# Node.net
KiCad netlist of a schematic drawn in EAGLE
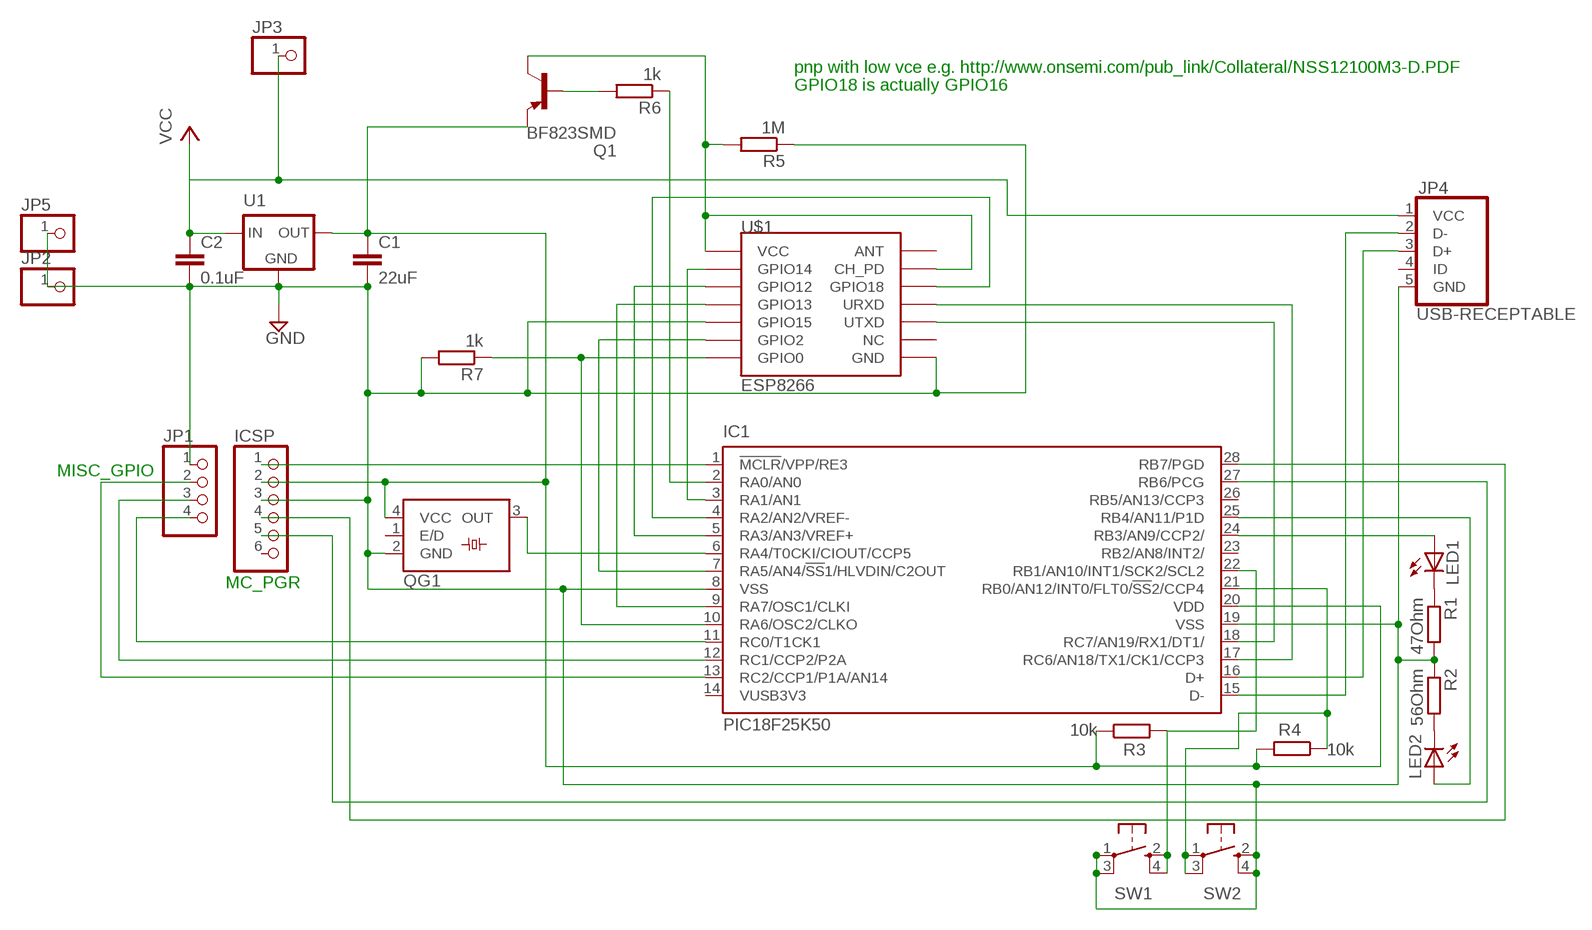
[diagram p0: schematic, sheet 1]

(export (version "E")
  (design (tool "Eeschema 10.0.6"))
  (components
    (comp (ref "C1")
      (value "22uF")
      (footprint "eagle-import:C0805")
      (libsource (lib "eagle-import") (part "C-EUC0805"))
    )
    (comp (ref "C2")
      (value "0.1uF")
      (footprint "eagle-import:C0805")
      (libsource (lib "eagle-import") (part "C-EUC0805"))
    )
    (comp (ref "IC1")
      (value "PIC18F25K50")
      (footprint "eagle-import:SO28W")
      (libsource (lib "eagle-import") (part "PIC18F25K50/SO-I"))
    )
    (comp (ref "ICSP")
      (value "PINHD-1X6")
      (footprint "eagle-import:1X06")
      (libsource (lib "eagle-import") (part "PINHD-1X6"))
    )
    (comp (ref "JP1")
      (value "PINHD-1X4")
      (footprint "eagle-import:1X04")
      (libsource (lib "eagle-import") (part "PINHD-1X4"))
    )
    (comp (ref "JP2")
      (value "PINHD-1X1")
      (footprint "eagle-import:1X01")
      (libsource (lib "eagle-import") (part "PINHD-1X1"))
    )
    (comp (ref "JP3")
      (value "PINHD-1X1")
      (footprint "eagle-import:1X01")
      (libsource (lib "eagle-import") (part "PINHD-1X1"))
    )
    (comp (ref "JP4")
      (value "USB-RECEPTABLE")
      (footprint "eagle-import:FCI-10103594-0001LF")
      (libsource (lib "eagle-import") (part "USB-RECEPTABLE"))
    )
    (comp (ref "JP5")
      (value "PINHD-1X1")
      (footprint "eagle-import:1X01")
      (libsource (lib "eagle-import") (part "PINHD-1X1"))
    )
    (comp (ref "LED1")
      (value "LEDCHIPLED_0805")
      (footprint "eagle-import:CHIPLED_0805")
      (libsource (lib "eagle-import") (part "LEDCHIPLED_0805"))
    )
    (comp (ref "LED2")
      (value "LEDCHIPLED_0805")
      (footprint "eagle-import:CHIPLED_0805")
      (libsource (lib "eagle-import") (part "LEDCHIPLED_0805"))
    )
    (comp (ref "Q1")
      (value "BF823SMD")
      (footprint "eagle-import:SOT23-BEC")
      (libsource (lib "eagle-import") (part "BF823SMD"))
    )
    (comp (ref "QG1")
      (value "SM77H")
      (footprint "eagle-import:SM77H")
      (libsource (lib "eagle-import") (part "SM77H"))
    )
    (comp (ref "R1")
      (value "47Ohm")
      (footprint "eagle-import:M0805")
      (libsource (lib "eagle-import") (part "R-EU_M0805"))
    )
    (comp (ref "R2")
      (value "56Ohm")
      (footprint "eagle-import:M0805")
      (libsource (lib "eagle-import") (part "R-EU_M0805"))
    )
    (comp (ref "R3")
      (value "10k")
      (footprint "eagle-import:M0805")
      (libsource (lib "eagle-import") (part "R-EU_M0805"))
    )
    (comp (ref "R4")
      (value "10k")
      (footprint "eagle-import:M0805")
      (libsource (lib "eagle-import") (part "R-EU_M0805"))
    )
    (comp (ref "R5")
      (value "1M")
      (footprint "eagle-import:M0805")
      (libsource (lib "eagle-import") (part "R-EU_M0805"))
    )
    (comp (ref "R6")
      (value "1k")
      (footprint "eagle-import:M0805")
      (libsource (lib "eagle-import") (part "R-EU_M0805"))
    )
    (comp (ref "R7")
      (value "1k")
      (footprint "eagle-import:M0805")
      (libsource (lib "eagle-import") (part "R-EU_M0805"))
    )
    (comp (ref "SW1")
      (value "SPST_TACT-KMR2")
      (footprint "eagle-import:KMR2")
      (libsource (lib "eagle-import") (part "SPST_TACT-KMR2"))
    )
    (comp (ref "SW2")
      (value "SPST_TACT-KMR2")
      (footprint "eagle-import:KMR2")
      (libsource (lib "eagle-import") (part "SPST_TACT-KMR2"))
    )
    (comp (ref "U$1")
      (value "ESP8266")
      (footprint "eagle-import:ESP-03")
      (libsource (lib "eagle-import") (part "ESP8266"))
    )
    (comp (ref "U1")
      (value "MIC5209-X.XYS")
      (footprint "eagle-import:SOT223")
      (libsource (lib "eagle-import") (part "MIC5209-X.XYS"))
    )
  )
  (nets
    (net (code "1") (name "GND") (class "Default")
      (node (ref "C1") (pin "2") (pinfunction "2_2") (pintype "passive"))
      (node (ref "C2") (pin "2") (pinfunction "2_2") (pintype "passive"))
      (node (ref "IC1") (pin "19") (pinfunction "VSS_19") (pintype "power_in"))
      (node (ref "IC1") (pin "8") (pinfunction "VSS_8") (pintype "power_in"))
      (node (ref "ICSP") (pin "3") (pinfunction "3_3") (pintype "passive"))
      (node (ref "JP1") (pin "1") (pinfunction "1_1") (pintype "passive"))
      (node (ref "JP2") (pin "1") (pinfunction "1_1") (pintype "passive"))
      (node (ref "JP4") (pin "5") (pinfunction "GND_5") (pintype "bidirectional"))
      (node (ref "JP5") (pin "1") (pinfunction "1_1") (pintype "passive"))
      (node (ref "QG1") (pin "2") (pinfunction "GND_2") (pintype "power_in"))
      (node (ref "R1") (pin "2") (pinfunction "2_2") (pintype "passive"))
      (node (ref "R2") (pin "1") (pinfunction "1_1") (pintype "passive"))
      (node (ref "R5") (pin "1") (pinfunction "1_1") (pintype "passive"))
      (node (ref "R7") (pin "2") (pinfunction "2_2") (pintype "passive"))
      (node (ref "SW1") (pin "1") (pinfunction "P_1") (pintype "passive"))
      (node (ref "SW1") (pin "3") (pinfunction "P1_3") (pintype "passive"))
      (node (ref "SW2") (pin "2") (pinfunction "S_2") (pintype "passive"))
      (node (ref "SW2") (pin "4") (pinfunction "S1_4") (pintype "passive"))
      (node (ref "U$1") (pin "GND") (pinfunction "GND_GND") (pintype "bidirectional"))
      (node (ref "U$1") (pin "GPIO15") (pinfunction "GPIO15_GPIO15") (pintype "bidirectional"))
      (node (ref "U1") (pin "2") (pinfunction "GND_2") (pintype "passive"))
      (node (ref "U1") (pin "4") (pinfunction "GND_4") (pintype "passive"))
    )
    (net (code "2") (name "Net-(IC1-D+)") (class "Default")
      (node (ref "IC1") (pin "16") (pinfunction "D+_16") (pintype "bidirectional"))
      (node (ref "JP4") (pin "3") (pinfunction "D+_3") (pintype "bidirectional"))
    )
    (net (code "3") (name "Net-(IC1-D-)") (class "Default")
      (node (ref "IC1") (pin "15") (pinfunction "D-_15") (pintype "bidirectional"))
      (node (ref "JP4") (pin "2") (pinfunction "D-_2") (pintype "bidirectional"))
    )
    (net (code "4") (name "Net-(IC1-RA0{slash}AN0)") (class "Default")
      (node (ref "IC1") (pin "2") (pinfunction "RA0/AN0_2") (pintype "bidirectional"))
      (node (ref "R6") (pin "1") (pinfunction "1_1") (pintype "passive"))
    )
    (net (code "5") (name "Net-(IC1-RA1{slash}AN1)") (class "Default")
      (node (ref "IC1") (pin "3") (pinfunction "RA1/AN1_3") (pintype "bidirectional"))
      (node (ref "U$1") (pin "GPIO14") (pinfunction "GPIO14_GPIO14") (pintype "bidirectional"))
    )
    (net (code "6") (name "Net-(IC1-RA2{slash}AN2{slash}VREF-)") (class "Default")
      (node (ref "IC1") (pin "4") (pinfunction "RA2/AN2/VREF-_4") (pintype "bidirectional"))
      (node (ref "U$1") (pin "GPIO18") (pinfunction "GPIO18_GPIO18") (pintype "bidirectional"))
    )
    (net (code "7") (name "Net-(IC1-RA3{slash}AN3{slash}VREF+)") (class "Default")
      (node (ref "IC1") (pin "5") (pinfunction "RA3/AN3/VREF+_5") (pintype "bidirectional"))
      (node (ref "U$1") (pin "GPIO12") (pinfunction "GPIO12_GPIO12") (pintype "bidirectional"))
    )
    (net (code "8") (name "Net-(IC1-RA4{slash}T0CKI{slash}CIOUT{slash}CCP5)") (class "Default")
      (node (ref "IC1") (pin "6") (pinfunction "RA4/T0CKI/CIOUT/CCP5_6") (pintype "bidirectional"))
      (node (ref "QG1") (pin "3") (pinfunction "OUT_3") (pintype "output"))
    )
    (net (code "9") (name "Net-(IC1-RA5{slash}AN4{slash}~{SS}1{slash}HLVDIN{slash}C2OUT)") (class "Default")
      (node (ref "IC1") (pin "7") (pinfunction "RA5/AN4/~{SS}1/HLVDIN/C2OUT_7") (pintype "bidirectional"))
      (node (ref "U$1") (pin "GPIO2") (pinfunction "GPIO2_GPIO2") (pintype "bidirectional"))
    )
    (net (code "10") (name "Net-(IC1-RA6{slash}OSC2{slash}CLKO)") (class "Default")
      (node (ref "IC1") (pin "10") (pinfunction "RA6/OSC2/CLKO_10") (pintype "output"))
      (node (ref "R7") (pin "1") (pinfunction "1_1") (pintype "passive"))
      (node (ref "U$1") (pin "GPIO0") (pinfunction "GPIO0_GPIO0") (pintype "bidirectional"))
    )
    (net (code "11") (name "Net-(IC1-RA7{slash}OSC1{slash}CLKI)") (class "Default")
      (node (ref "IC1") (pin "9") (pinfunction "RA7/OSC1/CLKI_9") (pintype "input"))
      (node (ref "U$1") (pin "GPIO13") (pinfunction "GPIO13_GPIO13") (pintype "bidirectional"))
    )
    (net (code "12") (name "Net-(IC1-RB0{slash}AN12{slash}INT0{slash}FLT0{slash}~{SS}2{slash}CCP4)") (class "Default")
      (node (ref "IC1") (pin "21") (pinfunction "RB0/AN12/INT0/FLT0/~{SS}2/CCP4_21") (pintype "bidirectional"))
      (node (ref "R4") (pin "1") (pinfunction "1_1") (pintype "passive"))
      (node (ref "SW2") (pin "1") (pinfunction "P_1") (pintype "passive"))
      (node (ref "SW2") (pin "3") (pinfunction "P1_3") (pintype "passive"))
    )
    (net (code "13") (name "Net-(IC1-RB1{slash}AN10{slash}INT1{slash}SCK2{slash}SCL2)") (class "Default")
      (node (ref "IC1") (pin "22") (pinfunction "RB1/AN10/INT1/SCK2/SCL2_22") (pintype "bidirectional"))
      (node (ref "R3") (pin "2") (pinfunction "2_2") (pintype "passive"))
      (node (ref "SW1") (pin "2") (pinfunction "S_2") (pintype "passive"))
      (node (ref "SW1") (pin "4") (pinfunction "S1_4") (pintype "passive"))
    )
    (net (code "14") (name "Net-(IC1-RB3{slash}AN9{slash}CCP2{slash})") (class "Default")
      (node (ref "IC1") (pin "24") (pinfunction "RB3/AN9/CCP2/_24") (pintype "bidirectional"))
      (node (ref "LED1") (pin "A") (pinfunction "A_A") (pintype "passive"))
    )
    (net (code "15") (name "Net-(IC1-RB4{slash}AN11{slash}P1D)") (class "Default")
      (node (ref "IC1") (pin "25") (pinfunction "RB4/AN11/P1D_25") (pintype "bidirectional"))
      (node (ref "LED2") (pin "A") (pinfunction "A_A") (pintype "passive"))
    )
    (net (code "16") (name "Net-(IC1-RB6{slash}PCG)") (class "Default")
      (node (ref "IC1") (pin "27") (pinfunction "RB6/PCG_27") (pintype "bidirectional"))
      (node (ref "ICSP") (pin "5") (pinfunction "5_5") (pintype "passive"))
    )
    (net (code "17") (name "Net-(IC1-RB7{slash}PGD)") (class "Default")
      (node (ref "IC1") (pin "28") (pinfunction "RB7/PGD_28") (pintype "bidirectional"))
      (node (ref "ICSP") (pin "4") (pinfunction "4_4") (pintype "passive"))
    )
    (net (code "18") (name "Net-(IC1-RC0{slash}T1CK1)") (class "Default")
      (node (ref "IC1") (pin "11") (pinfunction "RC0/T1CK1_11") (pintype "bidirectional"))
      (node (ref "JP1") (pin "4") (pinfunction "4_4") (pintype "passive"))
    )
    (net (code "19") (name "Net-(IC1-RC1{slash}CCP2{slash}P2A)") (class "Default")
      (node (ref "IC1") (pin "12") (pinfunction "RC1/CCP2/P2A_12") (pintype "bidirectional"))
      (node (ref "JP1") (pin "3") (pinfunction "3_3") (pintype "passive"))
    )
    (net (code "20") (name "Net-(IC1-RC2{slash}CCP1{slash}P1A{slash}AN14)") (class "Default")
      (node (ref "IC1") (pin "13") (pinfunction "RC2/CCP1/P1A/AN14_13") (pintype "bidirectional"))
      (node (ref "JP1") (pin "2") (pinfunction "2_2") (pintype "passive"))
    )
    (net (code "21") (name "Net-(IC1-RC6{slash}AN18{slash}TX1{slash}CK1{slash}CCP3)") (class "Default")
      (node (ref "IC1") (pin "17") (pinfunction "RC6/AN18/TX1/CK1/CCP3_17") (pintype "bidirectional"))
      (node (ref "U$1") (pin "URXD") (pinfunction "URXD_URXD") (pintype "bidirectional"))
    )
    (net (code "22") (name "Net-(IC1-RC7{slash}AN19{slash}RX1{slash}DT1{slash})") (class "Default")
      (node (ref "IC1") (pin "18") (pinfunction "RC7/AN19/RX1/DT1/_18") (pintype "bidirectional"))
      (node (ref "U$1") (pin "UTXD") (pinfunction "UTXD_UTXD") (pintype "bidirectional"))
    )
    (net (code "23") (name "Net-(IC1-VDD)") (class "Default")
      (node (ref "C1") (pin "1") (pinfunction "1_1") (pintype "passive"))
      (node (ref "IC1") (pin "20") (pinfunction "VDD_20") (pintype "power_in"))
      (node (ref "ICSP") (pin "2") (pinfunction "2_2") (pintype "passive"))
      (node (ref "Q1") (pin "E") (pinfunction "E_E") (pintype "passive"))
      (node (ref "QG1") (pin "4") (pinfunction "VCC_4") (pintype "power_in"))
      (node (ref "R3") (pin "1") (pinfunction "1_1") (pintype "passive"))
      (node (ref "R4") (pin "2") (pinfunction "2_2") (pintype "passive"))
      (node (ref "U1") (pin "3") (pinfunction "OUT_3") (pintype "passive"))
    )
    (net (code "24") (name "Net-(IC1-~{MCLR}{slash}VPP{slash}RE3)") (class "Default")
      (node (ref "IC1") (pin "1") (pinfunction "~{MCLR}/VPP/RE3_1") (pintype "input"))
      (node (ref "ICSP") (pin "1") (pinfunction "1_1") (pintype "passive"))
    )
    (net (code "25") (name "Net-(LED1-PadC)") (class "Default")
      (node (ref "LED1") (pin "C") (pinfunction "C_C") (pintype "passive"))
      (node (ref "R1") (pin "1") (pinfunction "1_1") (pintype "passive"))
    )
    (net (code "26") (name "Net-(LED2-PadC)") (class "Default")
      (node (ref "LED2") (pin "C") (pinfunction "C_C") (pintype "passive"))
      (node (ref "R2") (pin "2") (pinfunction "2_2") (pintype "passive"))
    )
    (net (code "27") (name "Net-(Q1-PadB)") (class "Default")
      (node (ref "Q1") (pin "B") (pinfunction "B_B") (pintype "passive"))
      (node (ref "R6") (pin "2") (pinfunction "2_2") (pintype "passive"))
    )
    (net (code "28") (name "Net-(Q1-PadC)") (class "Default")
      (node (ref "Q1") (pin "C") (pinfunction "C_C") (pintype "passive"))
      (node (ref "R5") (pin "2") (pinfunction "2_2") (pintype "passive"))
      (node (ref "U$1") (pin "CH_PD") (pinfunction "CH_PD_CH_PD") (pintype "bidirectional"))
      (node (ref "U$1") (pin "VCC") (pinfunction "VCC_VCC") (pintype "bidirectional"))
    )
    (net (code "29") (name "VCC") (class "Default")
      (node (ref "C2") (pin "1") (pinfunction "1_1") (pintype "passive"))
      (node (ref "JP3") (pin "1") (pinfunction "1_1") (pintype "passive"))
      (node (ref "JP4") (pin "1") (pinfunction "VCC_1") (pintype "bidirectional"))
      (node (ref "U1") (pin "1") (pinfunction "IN_1") (pintype "input"))
    )
    (net (code "30") (name "unconnected-(IC1-RB2{slash}AN8{slash}INT2{slash}-Pad23)") (class "Default")
      (node (ref "IC1") (pin "23") (pinfunction "RB2/AN8/INT2/_23") (pintype "bidirectional"))
    )
    (net (code "31") (name "unconnected-(IC1-RB5{slash}AN13{slash}CCP3-Pad26)") (class "Default")
      (node (ref "IC1") (pin "26") (pinfunction "RB5/AN13/CCP3_26") (pintype "bidirectional"))
    )
    (net (code "32") (name "unconnected-(IC1-VUSB3V3-Pad14)") (class "Default")
      (node (ref "IC1") (pin "14") (pinfunction "VUSB3V3_14") (pintype "bidirectional"))
    )
    (net (code "33") (name "unconnected-(ICSP-Pad6)") (class "Default")
      (node (ref "ICSP") (pin "6") (pinfunction "6_6") (pintype "passive"))
    )
    (net (code "34") (name "unconnected-(JP4-ID-Pad4)") (class "Default")
      (node (ref "JP4") (pin "4") (pinfunction "ID_4") (pintype "bidirectional"))
    )
    (net (code "35") (name "unconnected-(QG1-E{slash}D-Pad1)") (class "Default")
      (node (ref "QG1") (pin "1") (pinfunction "E/D_1") (pintype "input"))
    )
    (net (code "36") (name "unconnected-(U$1-PadANT)") (class "Default")
      (node (ref "U$1") (pin "ANT") (pinfunction "ANT_ANT") (pintype "bidirectional"))
    )
    (net (code "37") (name "unconnected-(U$1-PadNC)") (class "Default")
      (node (ref "U$1") (pin "NC") (pinfunction "NC_NC") (pintype "bidirectional"))
    )
  )
)
